# XibecaModuleTop.net
KiCad netlist of a schematic drawn in EAGLE
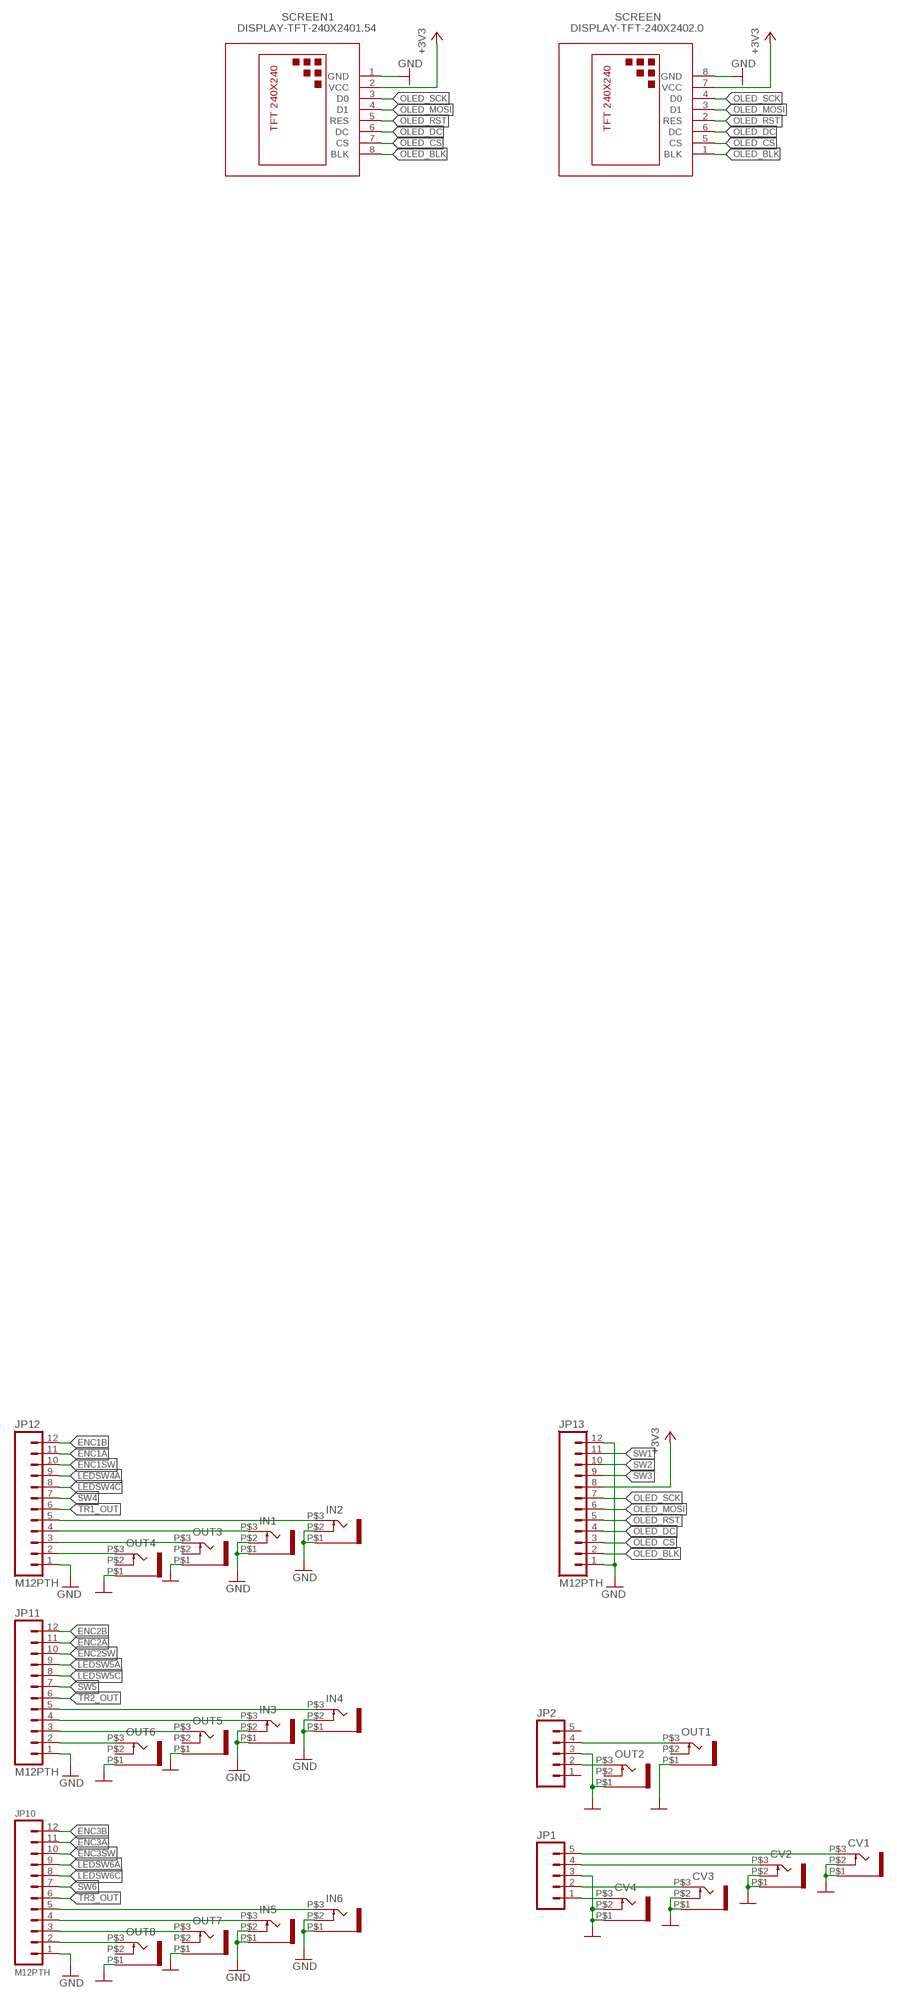
[diagram p0: schematic, sheet 1, part 1 of 2]
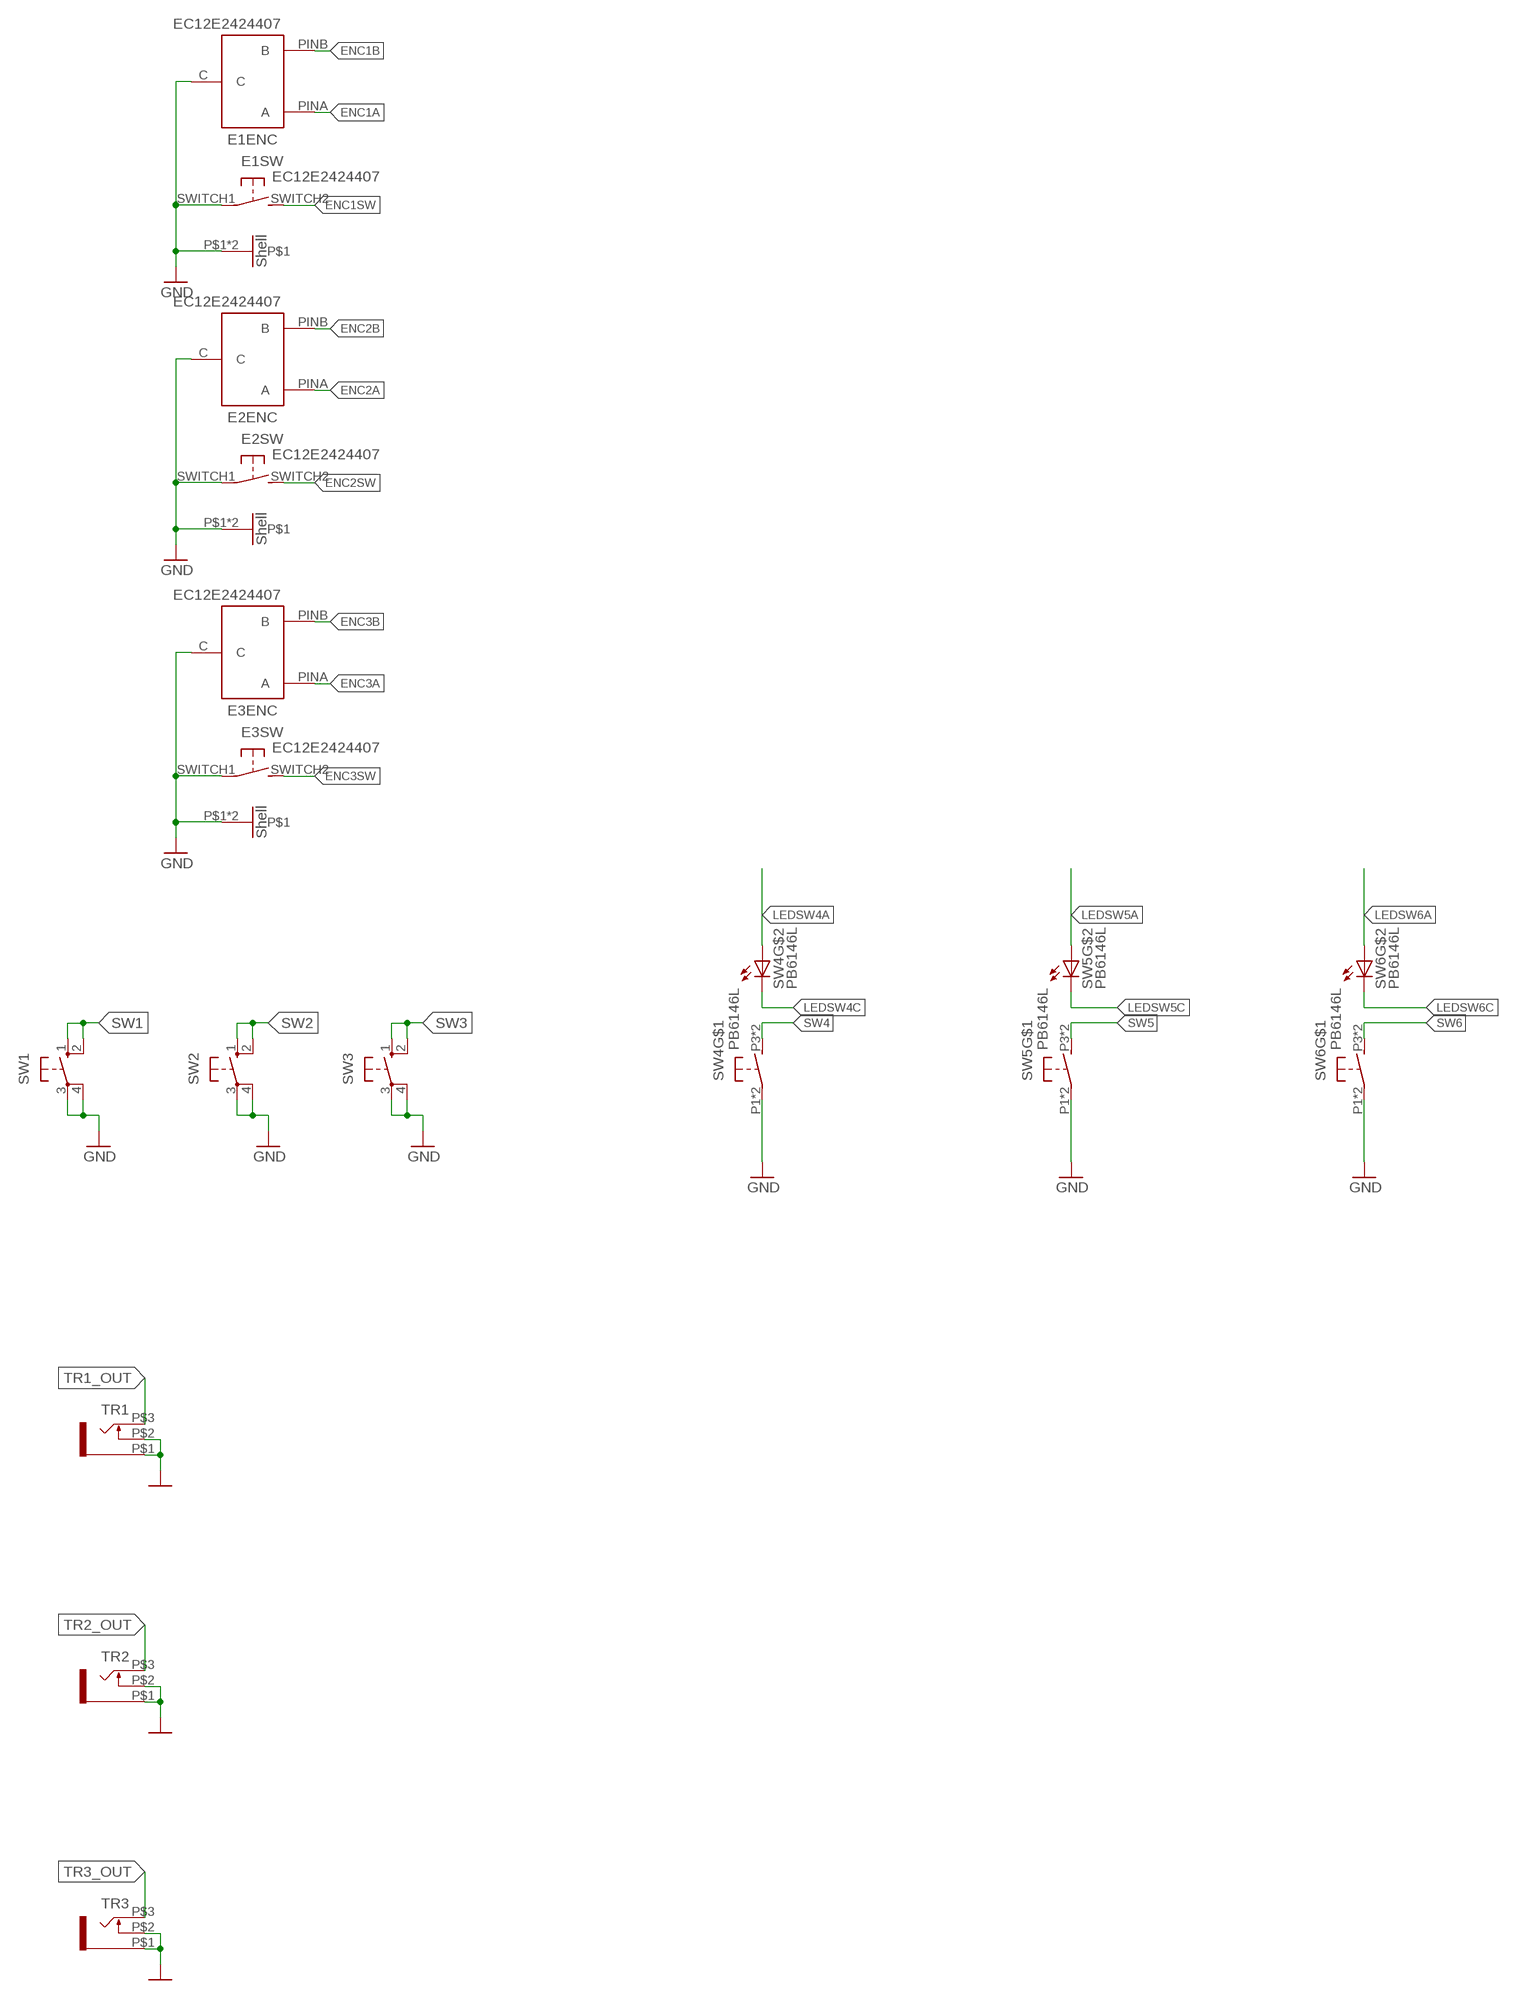
[diagram p1: schematic, sheet 1, part 2 of 2]

(export (version "E")
  (design (tool "Eeschema 10.0.6"))
  (components
    (comp (ref "CV1")
      (value "THONKICONN")
      (footprint "eagle-import:THONKICONN")
      (libsource (lib "eagle-import") (part "THONKICONN"))
    )
    (comp (ref "CV2")
      (value "THONKICONN")
      (footprint "eagle-import:THONKICONN")
      (libsource (lib "eagle-import") (part "THONKICONN"))
    )
    (comp (ref "CV3")
      (value "THONKICONN")
      (footprint "eagle-import:THONKICONN")
      (libsource (lib "eagle-import") (part "THONKICONN"))
    )
    (comp (ref "CV4")
      (value "THONKICONN")
      (footprint "eagle-import:THONKICONN")
      (libsource (lib "eagle-import") (part "THONKICONN"))
    )
    (comp (ref "E1")
      (value "EC12E2424407")
      (footprint "eagle-import:EC12E2424407")
      (libsource (lib "eagle-import") (part "EC12E2424407"))
    )
    (comp (ref "E2")
      (value "EC12E2424407")
      (footprint "eagle-import:EC12E2424407")
      (libsource (lib "eagle-import") (part "EC12E2424407"))
    )
    (comp (ref "E3")
      (value "EC12E2424407")
      (footprint "eagle-import:EC12E2424407")
      (libsource (lib "eagle-import") (part "EC12E2424407"))
    )
    (comp (ref "IN1")
      (value "THONKICONN")
      (footprint "eagle-import:THONKICONN")
      (libsource (lib "eagle-import") (part "THONKICONN"))
    )
    (comp (ref "IN2")
      (value "THONKICONN")
      (footprint "eagle-import:THONKICONN")
      (libsource (lib "eagle-import") (part "THONKICONN"))
    )
    (comp (ref "IN3")
      (value "THONKICONN")
      (footprint "eagle-import:THONKICONN")
      (libsource (lib "eagle-import") (part "THONKICONN"))
    )
    (comp (ref "IN4")
      (value "THONKICONN")
      (footprint "eagle-import:THONKICONN")
      (libsource (lib "eagle-import") (part "THONKICONN"))
    )
    (comp (ref "IN5")
      (value "THONKICONN")
      (footprint "eagle-import:THONKICONN")
      (libsource (lib "eagle-import") (part "THONKICONN"))
    )
    (comp (ref "IN6")
      (value "THONKICONN")
      (footprint "eagle-import:THONKICONN")
      (libsource (lib "eagle-import") (part "THONKICONN"))
    )
    (comp (ref "JP1")
      (value "M05PTH")
      (footprint "eagle-import:1X05")
      (libsource (lib "eagle-import") (part "M05PTH"))
    )
    (comp (ref "JP2")
      (value "M05PTH")
      (footprint "eagle-import:1X05")
      (libsource (lib "eagle-import") (part "M05PTH"))
    )
    (comp (ref "JP10")
      (value "M12PTH")
      (footprint "eagle-import:1X12")
      (libsource (lib "eagle-import") (part "M12PTH"))
    )
    (comp (ref "JP11")
      (value "M12PTH")
      (footprint "eagle-import:1X12")
      (libsource (lib "eagle-import") (part "M12PTH"))
    )
    (comp (ref "JP12")
      (value "M12PTH")
      (footprint "eagle-import:1X12")
      (libsource (lib "eagle-import") (part "M12PTH"))
    )
    (comp (ref "JP13")
      (value "M12PTH")
      (footprint "eagle-import:1X12")
      (libsource (lib "eagle-import") (part "M12PTH"))
    )
    (comp (ref "OUT1")
      (value "THONKICONN")
      (footprint "eagle-import:THONKICONN")
      (libsource (lib "eagle-import") (part "THONKICONN"))
    )
    (comp (ref "OUT2")
      (value "THONKICONN")
      (footprint "eagle-import:THONKICONN")
      (libsource (lib "eagle-import") (part "THONKICONN"))
    )
    (comp (ref "OUT3")
      (value "THONKICONN")
      (footprint "eagle-import:THONKICONN")
      (libsource (lib "eagle-import") (part "THONKICONN"))
    )
    (comp (ref "OUT4")
      (value "THONKICONN")
      (footprint "eagle-import:THONKICONN")
      (libsource (lib "eagle-import") (part "THONKICONN"))
    )
    (comp (ref "OUT5")
      (value "THONKICONN")
      (footprint "eagle-import:THONKICONN")
      (libsource (lib "eagle-import") (part "THONKICONN"))
    )
    (comp (ref "OUT6")
      (value "THONKICONN")
      (footprint "eagle-import:THONKICONN")
      (libsource (lib "eagle-import") (part "THONKICONN"))
    )
    (comp (ref "OUT7")
      (value "THONKICONN")
      (footprint "eagle-import:THONKICONN")
      (libsource (lib "eagle-import") (part "THONKICONN"))
    )
    (comp (ref "OUT8")
      (value "THONKICONN")
      (footprint "eagle-import:THONKICONN")
      (libsource (lib "eagle-import") (part "THONKICONN"))
    )
    (comp (ref "SCREEN")
      (value "DISPLAY-TFT-240X2402.0")
      (footprint "eagle-import:DISPLAY-TFT-240X320-2.0_")
      (libsource (lib "eagle-import") (part "DISPLAY-TFT-240X2402.0"))
    )
    (comp (ref "SCREEN1")
      (value "DISPLAY-TFT-240X2401.54")
      (footprint "eagle-import:DISPLAY-TFT-240X240-1.54_")
      (libsource (lib "eagle-import") (part "DISPLAY-TFT-240X2401.54"))
    )
    (comp (ref "SW1")
      (value "10-XX")
      (footprint "eagle-import:B3F-10XX")
      (fields (field (name "MPN") "B3F-1000"))
      (libsource (lib "eagle-import") (part "10-XX"))
    )
    (comp (ref "SW2")
      (value "10-XX")
      (footprint "eagle-import:B3F-10XX")
      (fields (field (name "MPN") "B3F-1000"))
      (libsource (lib "eagle-import") (part "10-XX"))
    )
    (comp (ref "SW3")
      (value "10-XX")
      (footprint "eagle-import:B3F-10XX")
      (fields (field (name "MPN") "B3F-1000"))
      (libsource (lib "eagle-import") (part "10-XX"))
    )
    (comp (ref "SW4")
      (value "PB6146L")
      (footprint "eagle-import:PB6146L")
      (libsource (lib "eagle-import") (part "PB6146L"))
    )
    (comp (ref "SW5")
      (value "PB6146L")
      (footprint "eagle-import:PB6146L")
      (libsource (lib "eagle-import") (part "PB6146L"))
    )
    (comp (ref "SW6")
      (value "PB6146L")
      (footprint "eagle-import:PB6146L")
      (libsource (lib "eagle-import") (part "PB6146L"))
    )
    (comp (ref "TR1")
      (value "THONKICONN")
      (footprint "eagle-import:THONKICONN")
      (libsource (lib "eagle-import") (part "THONKICONN"))
    )
    (comp (ref "TR2")
      (value "THONKICONN")
      (footprint "eagle-import:THONKICONN")
      (libsource (lib "eagle-import") (part "THONKICONN"))
    )
    (comp (ref "TR3")
      (value "THONKICONN")
      (footprint "eagle-import:THONKICONN")
      (libsource (lib "eagle-import") (part "THONKICONN"))
    )
  )
  (nets
    (net (code "1") (name "+3V3") (class "Default")
      (node (ref "JP13") (pin "8") (pinfunction "8_8") (pintype "passive"))
      (node (ref "SCREEN") (pin "7") (pinfunction "VCC_7") (pintype "power_in"))
      (node (ref "SCREEN1") (pin "2") (pinfunction "VCC_2") (pintype "power_in"))
    )
    (net (code "2") (name "ENC1A") (class "Default")
      (node (ref "E1") (pin "PINA") (pinfunction "A_PINA") (pintype "bidirectional"))
      (node (ref "JP12") (pin "11") (pinfunction "11_11") (pintype "passive"))
    )
    (net (code "3") (name "ENC1B") (class "Default")
      (node (ref "E1") (pin "PINB") (pinfunction "B_PINB") (pintype "bidirectional"))
      (node (ref "JP12") (pin "12") (pinfunction "12_12") (pintype "passive"))
    )
    (net (code "4") (name "ENC1SW") (class "Default")
      (node (ref "E1") (pin "SWITCH2") (pinfunction "S_SWITCH2") (pintype "passive"))
      (node (ref "JP12") (pin "10") (pinfunction "10_10") (pintype "passive"))
    )
    (net (code "5") (name "ENC2A") (class "Default")
      (node (ref "E2") (pin "PINA") (pinfunction "A_PINA") (pintype "bidirectional"))
      (node (ref "JP11") (pin "11") (pinfunction "11_11") (pintype "passive"))
    )
    (net (code "6") (name "ENC2B") (class "Default")
      (node (ref "E2") (pin "PINB") (pinfunction "B_PINB") (pintype "bidirectional"))
      (node (ref "JP11") (pin "12") (pinfunction "12_12") (pintype "passive"))
    )
    (net (code "7") (name "ENC2SW") (class "Default")
      (node (ref "E2") (pin "SWITCH2") (pinfunction "S_SWITCH2") (pintype "passive"))
      (node (ref "JP11") (pin "10") (pinfunction "10_10") (pintype "passive"))
    )
    (net (code "8") (name "ENC3A") (class "Default")
      (node (ref "E3") (pin "PINA") (pinfunction "A_PINA") (pintype "bidirectional"))
      (node (ref "JP10") (pin "11") (pinfunction "11_11") (pintype "passive"))
    )
    (net (code "9") (name "ENC3B") (class "Default")
      (node (ref "E3") (pin "PINB") (pinfunction "B_PINB") (pintype "bidirectional"))
      (node (ref "JP10") (pin "12") (pinfunction "12_12") (pintype "passive"))
    )
    (net (code "10") (name "ENC3SW") (class "Default")
      (node (ref "E3") (pin "SWITCH2") (pinfunction "S_SWITCH2") (pintype "passive"))
      (node (ref "JP10") (pin "10") (pinfunction "10_10") (pintype "passive"))
    )
    (net (code "11") (name "GND") (class "Default")
      (node (ref "CV1") (pin "P$1") (pinfunction "5_P$1") (pintype "passive"))
      (node (ref "CV1") (pin "P$2") (pinfunction "4_P$2") (pintype "passive"))
      (node (ref "CV2") (pin "P$1") (pinfunction "5_P$1") (pintype "passive"))
      (node (ref "CV2") (pin "P$2") (pinfunction "4_P$2") (pintype "passive"))
      (node (ref "CV3") (pin "P$1") (pinfunction "5_P$1") (pintype "passive"))
      (node (ref "CV3") (pin "P$2") (pinfunction "4_P$2") (pintype "passive"))
      (node (ref "CV4") (pin "P$1") (pinfunction "5_P$1") (pintype "passive"))
      (node (ref "CV4") (pin "P$2") (pinfunction "4_P$2") (pintype "passive"))
      (node (ref "E1") (pin "C") (pinfunction "C_C") (pintype "bidirectional"))
      (node (ref "E1") (pin "P$1") (pinfunction "P$1_P$1") (pintype "bidirectional"))
      (node (ref "E1") (pin "P$2") (pinfunction "P$1_P$2") (pintype "bidirectional"))
      (node (ref "E1") (pin "SWITCH1") (pinfunction "P_SWITCH1") (pintype "passive"))
      (node (ref "E2") (pin "C") (pinfunction "C_C") (pintype "bidirectional"))
      (node (ref "E2") (pin "P$1") (pinfunction "P$1_P$1") (pintype "bidirectional"))
      (node (ref "E2") (pin "P$2") (pinfunction "P$1_P$2") (pintype "bidirectional"))
      (node (ref "E2") (pin "SWITCH1") (pinfunction "P_SWITCH1") (pintype "passive"))
      (node (ref "E3") (pin "C") (pinfunction "C_C") (pintype "bidirectional"))
      (node (ref "E3") (pin "P$1") (pinfunction "P$1_P$1") (pintype "bidirectional"))
      (node (ref "E3") (pin "P$2") (pinfunction "P$1_P$2") (pintype "bidirectional"))
      (node (ref "E3") (pin "SWITCH1") (pinfunction "P_SWITCH1") (pintype "passive"))
      (node (ref "IN1") (pin "P$1") (pinfunction "5_P$1") (pintype "passive"))
      (node (ref "IN1") (pin "P$2") (pinfunction "4_P$2") (pintype "passive"))
      (node (ref "IN2") (pin "P$1") (pinfunction "5_P$1") (pintype "passive"))
      (node (ref "IN2") (pin "P$2") (pinfunction "4_P$2") (pintype "passive"))
      (node (ref "IN3") (pin "P$1") (pinfunction "5_P$1") (pintype "passive"))
      (node (ref "IN3") (pin "P$2") (pinfunction "4_P$2") (pintype "passive"))
      (node (ref "IN4") (pin "P$1") (pinfunction "5_P$1") (pintype "passive"))
      (node (ref "IN4") (pin "P$2") (pinfunction "4_P$2") (pintype "passive"))
      (node (ref "IN5") (pin "P$1") (pinfunction "5_P$1") (pintype "passive"))
      (node (ref "IN5") (pin "P$2") (pinfunction "4_P$2") (pintype "passive"))
      (node (ref "IN6") (pin "P$1") (pinfunction "5_P$1") (pintype "passive"))
      (node (ref "IN6") (pin "P$2") (pinfunction "4_P$2") (pintype "passive"))
      (node (ref "JP1") (pin "3") (pinfunction "3_3") (pintype "passive"))
      (node (ref "JP10") (pin "1") (pinfunction "1_1") (pintype "passive"))
      (node (ref "JP11") (pin "1") (pinfunction "1_1") (pintype "passive"))
      (node (ref "JP12") (pin "1") (pinfunction "1_1") (pintype "passive"))
      (node (ref "JP13") (pin "1") (pinfunction "1_1") (pintype "passive"))
      (node (ref "JP13") (pin "12") (pinfunction "12_12") (pintype "passive"))
      (node (ref "JP2") (pin "3") (pinfunction "3_3") (pintype "passive"))
      (node (ref "OUT1") (pin "P$1") (pinfunction "5_P$1") (pintype "passive"))
      (node (ref "OUT2") (pin "P$1") (pinfunction "5_P$1") (pintype "passive"))
      (node (ref "OUT3") (pin "P$1") (pinfunction "5_P$1") (pintype "passive"))
      (node (ref "OUT4") (pin "P$1") (pinfunction "5_P$1") (pintype "passive"))
      (node (ref "OUT5") (pin "P$1") (pinfunction "5_P$1") (pintype "passive"))
      (node (ref "OUT6") (pin "P$1") (pinfunction "5_P$1") (pintype "passive"))
      (node (ref "OUT7") (pin "P$1") (pinfunction "5_P$1") (pintype "passive"))
      (node (ref "OUT8") (pin "P$1") (pinfunction "5_P$1") (pintype "passive"))
      (node (ref "SCREEN") (pin "8") (pinfunction "GND_8") (pintype "power_in"))
      (node (ref "SCREEN1") (pin "1") (pinfunction "GND_1") (pintype "power_in"))
      (node (ref "SW1") (pin "3") (pinfunction "P_3") (pintype "passive"))
      (node (ref "SW1") (pin "4") (pinfunction "P1_4") (pintype "passive"))
      (node (ref "SW2") (pin "3") (pinfunction "P_3") (pintype "passive"))
      (node (ref "SW2") (pin "4") (pinfunction "P1_4") (pintype "passive"))
      (node (ref "SW3") (pin "3") (pinfunction "P_3") (pintype "passive"))
      (node (ref "SW3") (pin "4") (pinfunction "P1_4") (pintype "passive"))
      (node (ref "SW4") (pin "P1") (pinfunction "P_P1") (pintype "passive"))
      (node (ref "SW4") (pin "P2") (pinfunction "P_P2") (pintype "passive"))
      (node (ref "SW5") (pin "P1") (pinfunction "P_P1") (pintype "passive"))
      (node (ref "SW5") (pin "P2") (pinfunction "P_P2") (pintype "passive"))
      (node (ref "SW6") (pin "P1") (pinfunction "P_P1") (pintype "passive"))
      (node (ref "SW6") (pin "P2") (pinfunction "P_P2") (pintype "passive"))
      (node (ref "TR1") (pin "P$1") (pinfunction "5_P$1") (pintype "passive"))
      (node (ref "TR1") (pin "P$2") (pinfunction "4_P$2") (pintype "passive"))
      (node (ref "TR2") (pin "P$1") (pinfunction "5_P$1") (pintype "passive"))
      (node (ref "TR2") (pin "P$2") (pinfunction "4_P$2") (pintype "passive"))
      (node (ref "TR3") (pin "P$1") (pinfunction "5_P$1") (pintype "passive"))
      (node (ref "TR3") (pin "P$2") (pinfunction "4_P$2") (pintype "passive"))
    )
    (net (code "12") (name "LEDSW4A") (class "Default")
      (node (ref "JP12") (pin "9") (pinfunction "9_9") (pintype "passive"))
      (node (ref "SW4") (pin "PL1") (pinfunction "A_PL1") (pintype "passive"))
    )
    (net (code "13") (name "LEDSW4C") (class "Default")
      (node (ref "JP12") (pin "8") (pinfunction "8_8") (pintype "passive"))
      (node (ref "SW4") (pin "PL2") (pinfunction "C_PL2") (pintype "passive"))
    )
    (net (code "14") (name "LEDSW5A") (class "Default")
      (node (ref "JP11") (pin "9") (pinfunction "9_9") (pintype "passive"))
      (node (ref "SW5") (pin "PL1") (pinfunction "A_PL1") (pintype "passive"))
    )
    (net (code "15") (name "LEDSW5C") (class "Default")
      (node (ref "JP11") (pin "8") (pinfunction "8_8") (pintype "passive"))
      (node (ref "SW5") (pin "PL2") (pinfunction "C_PL2") (pintype "passive"))
    )
    (net (code "16") (name "LEDSW6A") (class "Default")
      (node (ref "JP10") (pin "9") (pinfunction "9_9") (pintype "passive"))
      (node (ref "SW6") (pin "PL1") (pinfunction "A_PL1") (pintype "passive"))
    )
    (net (code "17") (name "LEDSW6C") (class "Default")
      (node (ref "JP10") (pin "8") (pinfunction "8_8") (pintype "passive"))
      (node (ref "SW6") (pin "PL2") (pinfunction "C_PL2") (pintype "passive"))
    )
    (net (code "18") (name "Net-(CV1-3)") (class "Default")
      (node (ref "CV1") (pin "P$3") (pinfunction "3_P$3") (pintype "passive"))
      (node (ref "JP1") (pin "5") (pinfunction "5_5") (pintype "passive"))
    )
    (net (code "19") (name "Net-(CV2-3)") (class "Default")
      (node (ref "CV2") (pin "P$3") (pinfunction "3_P$3") (pintype "passive"))
      (node (ref "JP1") (pin "4") (pinfunction "4_4") (pintype "passive"))
    )
    (net (code "20") (name "Net-(CV3-3)") (class "Default")
      (node (ref "CV3") (pin "P$3") (pinfunction "3_P$3") (pintype "passive"))
      (node (ref "JP1") (pin "2") (pinfunction "2_2") (pintype "passive"))
    )
    (net (code "21") (name "Net-(CV4-3)") (class "Default")
      (node (ref "CV4") (pin "P$3") (pinfunction "3_P$3") (pintype "passive"))
      (node (ref "JP1") (pin "1") (pinfunction "1_1") (pintype "passive"))
    )
    (net (code "22") (name "Net-(IN1-3)") (class "Default")
      (node (ref "IN1") (pin "P$3") (pinfunction "3_P$3") (pintype "passive"))
      (node (ref "JP12") (pin "4") (pinfunction "4_4") (pintype "passive"))
    )
    (net (code "23") (name "Net-(IN2-3)") (class "Default")
      (node (ref "IN2") (pin "P$3") (pinfunction "3_P$3") (pintype "passive"))
      (node (ref "JP12") (pin "5") (pinfunction "5_5") (pintype "passive"))
    )
    (net (code "24") (name "Net-(IN3-3)") (class "Default")
      (node (ref "IN3") (pin "P$3") (pinfunction "3_P$3") (pintype "passive"))
      (node (ref "JP11") (pin "4") (pinfunction "4_4") (pintype "passive"))
    )
    (net (code "25") (name "Net-(IN4-3)") (class "Default")
      (node (ref "IN4") (pin "P$3") (pinfunction "3_P$3") (pintype "passive"))
      (node (ref "JP11") (pin "5") (pinfunction "5_5") (pintype "passive"))
    )
    (net (code "26") (name "Net-(IN5-3)") (class "Default")
      (node (ref "IN5") (pin "P$3") (pinfunction "3_P$3") (pintype "passive"))
      (node (ref "JP10") (pin "4") (pinfunction "4_4") (pintype "passive"))
    )
    (net (code "27") (name "Net-(IN6-3)") (class "Default")
      (node (ref "IN6") (pin "P$3") (pinfunction "3_P$3") (pintype "passive"))
      (node (ref "JP10") (pin "5") (pinfunction "5_5") (pintype "passive"))
    )
    (net (code "28") (name "Net-(OUT1-3)") (class "Default")
      (node (ref "JP2") (pin "4") (pinfunction "4_4") (pintype "passive"))
      (node (ref "OUT1") (pin "P$3") (pinfunction "3_P$3") (pintype "passive"))
    )
    (net (code "29") (name "Net-(OUT2-3)") (class "Default")
      (node (ref "JP2") (pin "2") (pinfunction "2_2") (pintype "passive"))
      (node (ref "OUT2") (pin "P$3") (pinfunction "3_P$3") (pintype "passive"))
    )
    (net (code "30") (name "Net-(OUT3-3)") (class "Default")
      (node (ref "JP12") (pin "3") (pinfunction "3_3") (pintype "passive"))
      (node (ref "OUT3") (pin "P$3") (pinfunction "3_P$3") (pintype "passive"))
    )
    (net (code "31") (name "Net-(OUT4-3)") (class "Default")
      (node (ref "JP12") (pin "2") (pinfunction "2_2") (pintype "passive"))
      (node (ref "OUT4") (pin "P$3") (pinfunction "3_P$3") (pintype "passive"))
    )
    (net (code "32") (name "Net-(OUT5-3)") (class "Default")
      (node (ref "JP11") (pin "3") (pinfunction "3_3") (pintype "passive"))
      (node (ref "OUT5") (pin "P$3") (pinfunction "3_P$3") (pintype "passive"))
    )
    (net (code "33") (name "Net-(OUT6-3)") (class "Default")
      (node (ref "JP11") (pin "2") (pinfunction "2_2") (pintype "passive"))
      (node (ref "OUT6") (pin "P$3") (pinfunction "3_P$3") (pintype "passive"))
    )
    (net (code "34") (name "Net-(OUT7-3)") (class "Default")
      (node (ref "JP10") (pin "3") (pinfunction "3_3") (pintype "passive"))
      (node (ref "OUT7") (pin "P$3") (pinfunction "3_P$3") (pintype "passive"))
    )
    (net (code "35") (name "Net-(OUT8-3)") (class "Default")
      (node (ref "JP10") (pin "2") (pinfunction "2_2") (pintype "passive"))
      (node (ref "OUT8") (pin "P$3") (pinfunction "3_P$3") (pintype "passive"))
    )
    (net (code "36") (name "OLED_BLK") (class "Default")
      (node (ref "JP13") (pin "2") (pinfunction "2_2") (pintype "passive"))
      (node (ref "SCREEN") (pin "1") (pinfunction "BLK_1") (pintype "bidirectional"))
      (node (ref "SCREEN1") (pin "8") (pinfunction "BLK_8") (pintype "bidirectional"))
    )
    (net (code "37") (name "OLED_CS") (class "Default")
      (node (ref "JP13") (pin "3") (pinfunction "3_3") (pintype "passive"))
      (node (ref "SCREEN") (pin "5") (pinfunction "CS_5") (pintype "bidirectional"))
      (node (ref "SCREEN1") (pin "7") (pinfunction "CS_7") (pintype "bidirectional"))
    )
    (net (code "38") (name "OLED_DC") (class "Default")
      (node (ref "JP13") (pin "4") (pinfunction "4_4") (pintype "passive"))
      (node (ref "SCREEN") (pin "6") (pinfunction "DC_6") (pintype "bidirectional"))
      (node (ref "SCREEN1") (pin "6") (pinfunction "DC_6") (pintype "bidirectional"))
    )
    (net (code "39") (name "OLED_MOSI") (class "Default")
      (node (ref "JP13") (pin "6") (pinfunction "6_6") (pintype "passive"))
      (node (ref "SCREEN") (pin "3") (pinfunction "D1_3") (pintype "bidirectional"))
      (node (ref "SCREEN1") (pin "4") (pinfunction "D1_4") (pintype "bidirectional"))
    )
    (net (code "40") (name "OLED_RST") (class "Default")
      (node (ref "JP13") (pin "5") (pinfunction "5_5") (pintype "passive"))
      (node (ref "SCREEN") (pin "2") (pinfunction "RES_2") (pintype "bidirectional"))
      (node (ref "SCREEN1") (pin "5") (pinfunction "RES_5") (pintype "bidirectional"))
    )
    (net (code "41") (name "OLED_SCK") (class "Default")
      (node (ref "JP13") (pin "7") (pinfunction "7_7") (pintype "passive"))
      (node (ref "SCREEN") (pin "4") (pinfunction "D0_4") (pintype "bidirectional"))
      (node (ref "SCREEN1") (pin "3") (pinfunction "D0_3") (pintype "bidirectional"))
    )
    (net (code "42") (name "SW1") (class "Default")
      (node (ref "JP13") (pin "11") (pinfunction "11_11") (pintype "passive"))
      (node (ref "SW1") (pin "1") (pinfunction "S_1") (pintype "passive"))
      (node (ref "SW1") (pin "2") (pinfunction "S1_2") (pintype "passive"))
    )
    (net (code "43") (name "SW2") (class "Default")
      (node (ref "JP13") (pin "10") (pinfunction "10_10") (pintype "passive"))
      (node (ref "SW2") (pin "1") (pinfunction "S_1") (pintype "passive"))
      (node (ref "SW2") (pin "2") (pinfunction "S1_2") (pintype "passive"))
    )
    (net (code "44") (name "SW3") (class "Default")
      (node (ref "JP13") (pin "9") (pinfunction "9_9") (pintype "passive"))
      (node (ref "SW3") (pin "1") (pinfunction "S_1") (pintype "passive"))
      (node (ref "SW3") (pin "2") (pinfunction "S1_2") (pintype "passive"))
    )
    (net (code "45") (name "SW4") (class "Default")
      (node (ref "JP12") (pin "7") (pinfunction "7_7") (pintype "passive"))
      (node (ref "SW4") (pin "P3") (pinfunction "S_P3") (pintype "passive"))
      (node (ref "SW4") (pin "P4") (pinfunction "S_P4") (pintype "passive"))
    )
    (net (code "46") (name "SW5") (class "Default")
      (node (ref "JP11") (pin "7") (pinfunction "7_7") (pintype "passive"))
      (node (ref "SW5") (pin "P3") (pinfunction "S_P3") (pintype "passive"))
      (node (ref "SW5") (pin "P4") (pinfunction "S_P4") (pintype "passive"))
    )
    (net (code "47") (name "SW6") (class "Default")
      (node (ref "JP10") (pin "7") (pinfunction "7_7") (pintype "passive"))
      (node (ref "SW6") (pin "P3") (pinfunction "S_P3") (pintype "passive"))
      (node (ref "SW6") (pin "P4") (pinfunction "S_P4") (pintype "passive"))
    )
    (net (code "48") (name "TR1_OUT") (class "Default")
      (node (ref "JP12") (pin "6") (pinfunction "6_6") (pintype "passive"))
      (node (ref "TR1") (pin "P$3") (pinfunction "3_P$3") (pintype "passive"))
    )
    (net (code "49") (name "TR2_OUT") (class "Default")
      (node (ref "JP11") (pin "6") (pinfunction "6_6") (pintype "passive"))
      (node (ref "TR2") (pin "P$3") (pinfunction "3_P$3") (pintype "passive"))
    )
    (net (code "50") (name "TR3_OUT") (class "Default")
      (node (ref "JP10") (pin "6") (pinfunction "6_6") (pintype "passive"))
      (node (ref "TR3") (pin "P$3") (pinfunction "3_P$3") (pintype "passive"))
    )
    (net (code "51") (name "unconnected-(JP2-Pad1)") (class "Default")
      (node (ref "JP2") (pin "1") (pinfunction "1_1") (pintype "passive"))
    )
    (net (code "52") (name "unconnected-(JP2-Pad5)") (class "Default")
      (node (ref "JP2") (pin "5") (pinfunction "5_5") (pintype "passive"))
    )
    (net (code "53") (name "unconnected-(OUT1-4-PadP$2)") (class "Default")
      (node (ref "OUT1") (pin "P$2") (pinfunction "4_P$2") (pintype "passive"))
    )
    (net (code "54") (name "unconnected-(OUT2-4-PadP$2)") (class "Default")
      (node (ref "OUT2") (pin "P$2") (pinfunction "4_P$2") (pintype "passive"))
    )
    (net (code "55") (name "unconnected-(OUT3-4-PadP$2)") (class "Default")
      (node (ref "OUT3") (pin "P$2") (pinfunction "4_P$2") (pintype "passive"))
    )
    (net (code "56") (name "unconnected-(OUT4-4-PadP$2)") (class "Default")
      (node (ref "OUT4") (pin "P$2") (pinfunction "4_P$2") (pintype "passive"))
    )
    (net (code "57") (name "unconnected-(OUT5-4-PadP$2)") (class "Default")
      (node (ref "OUT5") (pin "P$2") (pinfunction "4_P$2") (pintype "passive"))
    )
    (net (code "58") (name "unconnected-(OUT6-4-PadP$2)") (class "Default")
      (node (ref "OUT6") (pin "P$2") (pinfunction "4_P$2") (pintype "passive"))
    )
    (net (code "59") (name "unconnected-(OUT7-4-PadP$2)") (class "Default")
      (node (ref "OUT7") (pin "P$2") (pinfunction "4_P$2") (pintype "passive"))
    )
    (net (code "60") (name "unconnected-(OUT8-4-PadP$2)") (class "Default")
      (node (ref "OUT8") (pin "P$2") (pinfunction "4_P$2") (pintype "passive"))
    )
  )
)
